# dumbpad.net
KiCad netlist of a schematic drawn in EAGLE
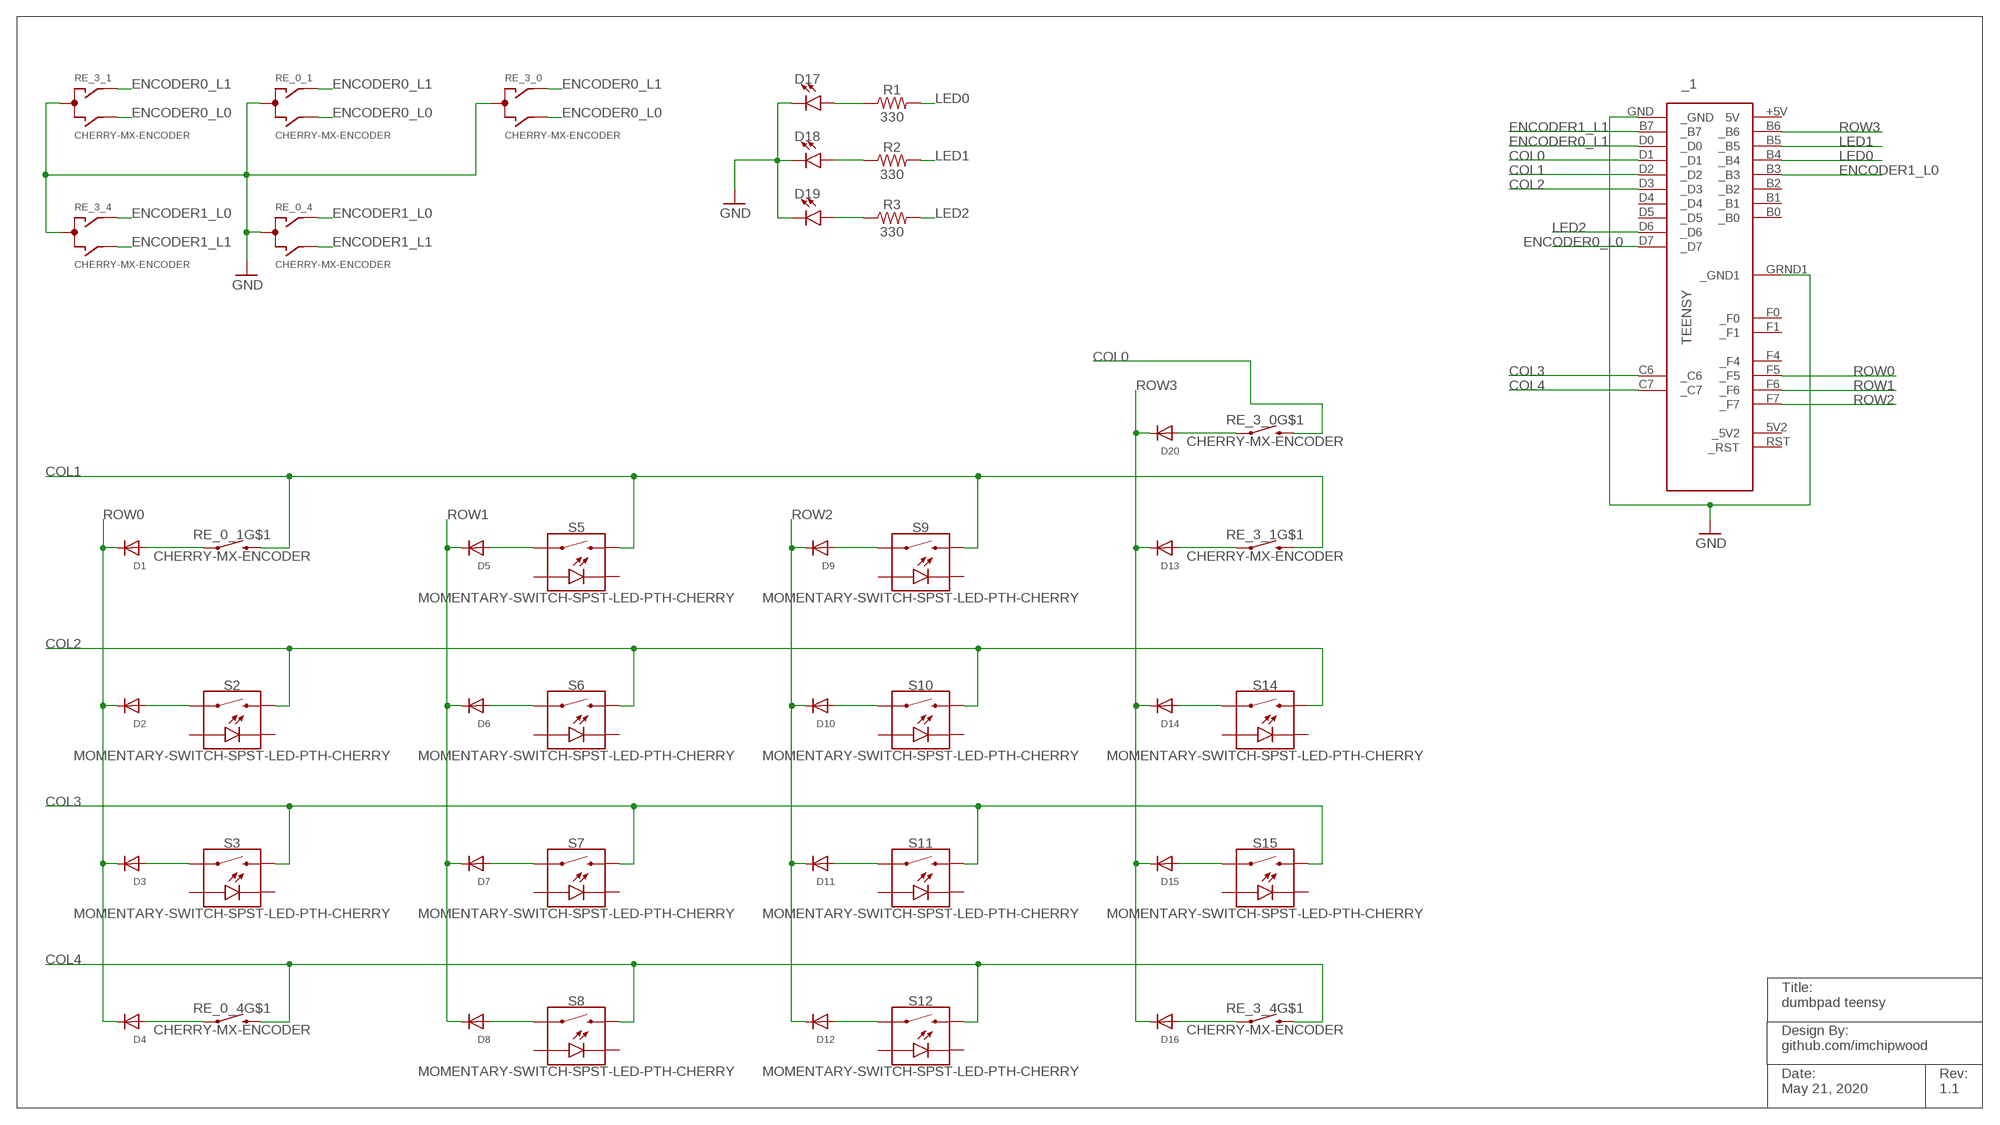
[diagram p0: schematic, sheet 1]

(export (version "E")
  (design (tool "Eeschema 10.0.6"))
  (components
    (comp (ref "D1")
      (value "DIODEDO-1N4148")
      (footprint "eagle-import:DO-1N4148")
      (libsource (lib "eagle-import") (part "DIODEDO-1N4148"))
    )
    (comp (ref "D2")
      (value "DIODEDO-1N4148")
      (footprint "eagle-import:DO-1N4148")
      (libsource (lib "eagle-import") (part "DIODEDO-1N4148"))
    )
    (comp (ref "D3")
      (value "DIODEDO-1N4148")
      (footprint "eagle-import:DO-1N4148")
      (libsource (lib "eagle-import") (part "DIODEDO-1N4148"))
    )
    (comp (ref "D4")
      (value "DIODEDO-1N4148")
      (footprint "eagle-import:DO-1N4148")
      (libsource (lib "eagle-import") (part "DIODEDO-1N4148"))
    )
    (comp (ref "D5")
      (value "DIODEDO-1N4148")
      (footprint "eagle-import:DO-1N4148")
      (libsource (lib "eagle-import") (part "DIODEDO-1N4148"))
    )
    (comp (ref "D6")
      (value "DIODEDO-1N4148")
      (footprint "eagle-import:DO-1N4148")
      (libsource (lib "eagle-import") (part "DIODEDO-1N4148"))
    )
    (comp (ref "D7")
      (value "DIODEDO-1N4148")
      (footprint "eagle-import:DO-1N4148")
      (libsource (lib "eagle-import") (part "DIODEDO-1N4148"))
    )
    (comp (ref "D8")
      (value "DIODEDO-1N4148")
      (footprint "eagle-import:DO-1N4148")
      (libsource (lib "eagle-import") (part "DIODEDO-1N4148"))
    )
    (comp (ref "D9")
      (value "DIODEDO-1N4148")
      (footprint "eagle-import:DO-1N4148")
      (libsource (lib "eagle-import") (part "DIODEDO-1N4148"))
    )
    (comp (ref "D10")
      (value "DIODEDO-1N4148")
      (footprint "eagle-import:DO-1N4148")
      (libsource (lib "eagle-import") (part "DIODEDO-1N4148"))
    )
    (comp (ref "D11")
      (value "DIODEDO-1N4148")
      (footprint "eagle-import:DO-1N4148")
      (libsource (lib "eagle-import") (part "DIODEDO-1N4148"))
    )
    (comp (ref "D12")
      (value "DIODEDO-1N4148")
      (footprint "eagle-import:DO-1N4148")
      (libsource (lib "eagle-import") (part "DIODEDO-1N4148"))
    )
    (comp (ref "D13")
      (value "DIODEDO-1N4148")
      (footprint "eagle-import:DO-1N4148")
      (libsource (lib "eagle-import") (part "DIODEDO-1N4148"))
    )
    (comp (ref "D14")
      (value "DIODEDO-1N4148")
      (footprint "eagle-import:DO-1N4148")
      (libsource (lib "eagle-import") (part "DIODEDO-1N4148"))
    )
    (comp (ref "D15")
      (value "DIODEDO-1N4148")
      (footprint "eagle-import:DO-1N4148")
      (libsource (lib "eagle-import") (part "DIODEDO-1N4148"))
    )
    (comp (ref "D16")
      (value "DIODEDO-1N4148")
      (footprint "eagle-import:DO-1N4148")
      (libsource (lib "eagle-import") (part "DIODEDO-1N4148"))
    )
    (comp (ref "D17")
      (value "LED3MM")
      (footprint "eagle-import:LED_3MM")
      (libsource (lib "eagle-import") (part "LED3MM"))
    )
    (comp (ref "D18")
      (value "LED3MM")
      (footprint "eagle-import:LED_3MM")
      (libsource (lib "eagle-import") (part "LED3MM"))
    )
    (comp (ref "D19")
      (value "LED3MM")
      (footprint "eagle-import:LED_3MM")
      (libsource (lib "eagle-import") (part "LED3MM"))
    )
    (comp (ref "D20")
      (value "DIODEDO-1N4148")
      (footprint "eagle-import:DO-1N4148")
      (libsource (lib "eagle-import") (part "DIODEDO-1N4148"))
    )
    (comp (ref "R1")
      (value "330")
      (footprint "eagle-import:AXIAL-0.3")
      (libsource (lib "eagle-import") (part "330OHM-HORIZ-1/10W-5%"))
    )
    (comp (ref "R2")
      (value "330")
      (footprint "eagle-import:AXIAL-0.3")
      (libsource (lib "eagle-import") (part "330OHM-HORIZ-1/10W-5%"))
    )
    (comp (ref "R3")
      (value "330")
      (footprint "eagle-import:AXIAL-0.3")
      (libsource (lib "eagle-import") (part "330OHM-HORIZ-1/10W-5%"))
    )
    (comp (ref "RE_0_1")
      (value "CHERRY-MX-ENCODER")
      (footprint "eagle-import:CHERRY-MX-ENCODER")
      (libsource (lib "eagle-import") (part "CHERRY-MX-ENCODER"))
    )
    (comp (ref "RE_0_4")
      (value "CHERRY-MX-ENCODER")
      (footprint "eagle-import:CHERRY-MX-ENCODER")
      (libsource (lib "eagle-import") (part "CHERRY-MX-ENCODER"))
    )
    (comp (ref "RE_3_0")
      (value "CHERRY-MX-ENCODER")
      (footprint "eagle-import:CHERRY-MX-ENCODER")
      (libsource (lib "eagle-import") (part "CHERRY-MX-ENCODER"))
    )
    (comp (ref "RE_3_1")
      (value "CHERRY-MX-ENCODER")
      (footprint "eagle-import:CHERRY-MX-ENCODER")
      (libsource (lib "eagle-import") (part "CHERRY-MX-ENCODER"))
    )
    (comp (ref "RE_3_4")
      (value "CHERRY-MX-ENCODER")
      (footprint "eagle-import:CHERRY-MX-ENCODER")
      (libsource (lib "eagle-import") (part "CHERRY-MX-ENCODER"))
    )
    (comp (ref "S2")
      (value "MOMENTARY-SWITCH-SPST-LED-PTH-CHERRY")
      (footprint "eagle-import:CHERRY-MX-LED")
      (libsource (lib "eagle-import") (part "MOMENTARY-SWITCH-SPST-LED-PTH-CHERRY"))
    )
    (comp (ref "S3")
      (value "MOMENTARY-SWITCH-SPST-LED-PTH-CHERRY")
      (footprint "eagle-import:CHERRY-MX-LED")
      (libsource (lib "eagle-import") (part "MOMENTARY-SWITCH-SPST-LED-PTH-CHERRY"))
    )
    (comp (ref "S5")
      (value "MOMENTARY-SWITCH-SPST-LED-PTH-CHERRY")
      (footprint "eagle-import:CHERRY-MX-LED")
      (libsource (lib "eagle-import") (part "MOMENTARY-SWITCH-SPST-LED-PTH-CHERRY"))
    )
    (comp (ref "S6")
      (value "MOMENTARY-SWITCH-SPST-LED-PTH-CHERRY")
      (footprint "eagle-import:CHERRY-MX-LED")
      (libsource (lib "eagle-import") (part "MOMENTARY-SWITCH-SPST-LED-PTH-CHERRY"))
    )
    (comp (ref "S7")
      (value "MOMENTARY-SWITCH-SPST-LED-PTH-CHERRY")
      (footprint "eagle-import:CHERRY-MX-LED")
      (libsource (lib "eagle-import") (part "MOMENTARY-SWITCH-SPST-LED-PTH-CHERRY"))
    )
    (comp (ref "S8")
      (value "MOMENTARY-SWITCH-SPST-LED-PTH-CHERRY")
      (footprint "eagle-import:CHERRY-MX-LED")
      (libsource (lib "eagle-import") (part "MOMENTARY-SWITCH-SPST-LED-PTH-CHERRY"))
    )
    (comp (ref "S9")
      (value "MOMENTARY-SWITCH-SPST-LED-PTH-CHERRY")
      (footprint "eagle-import:CHERRY-MX-LED")
      (libsource (lib "eagle-import") (part "MOMENTARY-SWITCH-SPST-LED-PTH-CHERRY"))
    )
    (comp (ref "S10")
      (value "MOMENTARY-SWITCH-SPST-LED-PTH-CHERRY")
      (footprint "eagle-import:CHERRY-MX-LED")
      (libsource (lib "eagle-import") (part "MOMENTARY-SWITCH-SPST-LED-PTH-CHERRY"))
    )
    (comp (ref "S11")
      (value "MOMENTARY-SWITCH-SPST-LED-PTH-CHERRY")
      (footprint "eagle-import:CHERRY-MX-LED")
      (libsource (lib "eagle-import") (part "MOMENTARY-SWITCH-SPST-LED-PTH-CHERRY"))
    )
    (comp (ref "S12")
      (value "MOMENTARY-SWITCH-SPST-LED-PTH-CHERRY")
      (footprint "eagle-import:CHERRY-MX-LED")
      (libsource (lib "eagle-import") (part "MOMENTARY-SWITCH-SPST-LED-PTH-CHERRY"))
    )
    (comp (ref "S14")
      (value "MOMENTARY-SWITCH-SPST-LED-PTH-CHERRY")
      (footprint "eagle-import:CHERRY-MX-LED")
      (libsource (lib "eagle-import") (part "MOMENTARY-SWITCH-SPST-LED-PTH-CHERRY"))
    )
    (comp (ref "S15")
      (value "MOMENTARY-SWITCH-SPST-LED-PTH-CHERRY")
      (footprint "eagle-import:CHERRY-MX-LED")
      (libsource (lib "eagle-import") (part "MOMENTARY-SWITCH-SPST-LED-PTH-CHERRY"))
    )
    (comp (ref "_1")
      (value "TEENSY")
      (footprint "eagle-import:TEENSY")
      (libsource (lib "eagle-import") (part "TEENSY"))
    )
  )
  (nets
    (net (code "1") (name "/COL0") (class "Default")
      (node (ref "RE_3_0") (pin "E") (pinfunction "2_E") (pintype "passive"))
      (node (ref "RE_3_0") (pin "S2") (pinfunction "2_S2") (pintype "passive"))
      (node (ref "_1") (pin "D1") (pinfunction "_D1_D1") (pintype "bidirectional"))
    )
    (net (code "2") (name "/COL1") (class "Default")
      (node (ref "RE_0_1") (pin "E") (pinfunction "2_E") (pintype "passive"))
      (node (ref "RE_0_1") (pin "S2") (pinfunction "2_S2") (pintype "passive"))
      (node (ref "RE_3_1") (pin "E") (pinfunction "2_E") (pintype "passive"))
      (node (ref "RE_3_1") (pin "S2") (pinfunction "2_S2") (pintype "passive"))
      (node (ref "S5") (pin "S2") (pinfunction "2_S2") (pintype "passive"))
      (node (ref "S9") (pin "S2") (pinfunction "2_S2") (pintype "passive"))
      (node (ref "_1") (pin "D2") (pinfunction "_D2_D2") (pintype "bidirectional"))
    )
    (net (code "3") (name "/COL2") (class "Default")
      (node (ref "S10") (pin "S2") (pinfunction "2_S2") (pintype "passive"))
      (node (ref "S14") (pin "S2") (pinfunction "2_S2") (pintype "passive"))
      (node (ref "S2") (pin "S2") (pinfunction "2_S2") (pintype "passive"))
      (node (ref "S6") (pin "S2") (pinfunction "2_S2") (pintype "passive"))
      (node (ref "_1") (pin "D3") (pinfunction "_D3_D3") (pintype "bidirectional"))
    )
    (net (code "4") (name "/COL3") (class "Default")
      (node (ref "S11") (pin "S2") (pinfunction "2_S2") (pintype "passive"))
      (node (ref "S15") (pin "S2") (pinfunction "2_S2") (pintype "passive"))
      (node (ref "S3") (pin "S2") (pinfunction "2_S2") (pintype "passive"))
      (node (ref "S7") (pin "S2") (pinfunction "2_S2") (pintype "passive"))
      (node (ref "_1") (pin "C6") (pinfunction "_C6_C6") (pintype "bidirectional"))
    )
    (net (code "5") (name "/COL4") (class "Default")
      (node (ref "RE_0_4") (pin "E") (pinfunction "2_E") (pintype "passive"))
      (node (ref "RE_0_4") (pin "S2") (pinfunction "2_S2") (pintype "passive"))
      (node (ref "RE_3_4") (pin "E") (pinfunction "2_E") (pintype "passive"))
      (node (ref "RE_3_4") (pin "S2") (pinfunction "2_S2") (pintype "passive"))
      (node (ref "S12") (pin "S2") (pinfunction "2_S2") (pintype "passive"))
      (node (ref "S8") (pin "S2") (pinfunction "2_S2") (pintype "passive"))
      (node (ref "_1") (pin "C7") (pinfunction "_C7_C7") (pintype "bidirectional"))
    )
    (net (code "6") (name "/ENCODER0_L0") (class "Default")
      (node (ref "RE_0_1") (pin "B") (pinfunction "B_B") (pintype "passive"))
      (node (ref "RE_3_0") (pin "B") (pinfunction "B_B") (pintype "passive"))
      (node (ref "RE_3_1") (pin "B") (pinfunction "B_B") (pintype "passive"))
      (node (ref "_1") (pin "D7") (pinfunction "_D7_D7") (pintype "bidirectional"))
    )
    (net (code "7") (name "/ENCODER0_L1") (class "Default")
      (node (ref "RE_0_1") (pin "A") (pinfunction "A_A") (pintype "passive"))
      (node (ref "RE_3_0") (pin "A") (pinfunction "A_A") (pintype "passive"))
      (node (ref "RE_3_1") (pin "A") (pinfunction "A_A") (pintype "passive"))
      (node (ref "_1") (pin "D0") (pinfunction "_D0_D0") (pintype "bidirectional"))
    )
    (net (code "8") (name "/ENCODER1_L0") (class "Default")
      (node (ref "RE_0_4") (pin "A") (pinfunction "A_A") (pintype "passive"))
      (node (ref "RE_3_4") (pin "A") (pinfunction "A_A") (pintype "passive"))
      (node (ref "_1") (pin "B3") (pinfunction "_B3_B3") (pintype "bidirectional"))
    )
    (net (code "9") (name "/ENCODER1_L1") (class "Default")
      (node (ref "RE_0_4") (pin "B") (pinfunction "B_B") (pintype "passive"))
      (node (ref "RE_3_4") (pin "B") (pinfunction "B_B") (pintype "passive"))
      (node (ref "_1") (pin "B7") (pinfunction "_B7_B7") (pintype "bidirectional"))
    )
    (net (code "10") (name "/LED0") (class "Default")
      (node (ref "R1") (pin "P$2") (pinfunction "2_P$2") (pintype "passive"))
      (node (ref "_1") (pin "B4") (pinfunction "_B4_B4") (pintype "bidirectional"))
    )
    (net (code "11") (name "/LED1") (class "Default")
      (node (ref "R2") (pin "P$2") (pinfunction "2_P$2") (pintype "passive"))
      (node (ref "_1") (pin "B5") (pinfunction "_B5_B5") (pintype "bidirectional"))
    )
    (net (code "12") (name "/LED2") (class "Default")
      (node (ref "R3") (pin "P$2") (pinfunction "2_P$2") (pintype "passive"))
      (node (ref "_1") (pin "D6") (pinfunction "_D6_D6") (pintype "bidirectional"))
    )
    (net (code "13") (name "/ROW0") (class "Default")
      (node (ref "D1") (pin "C") (pinfunction "C_C") (pintype "passive"))
      (node (ref "D2") (pin "C") (pinfunction "C_C") (pintype "passive"))
      (node (ref "D3") (pin "C") (pinfunction "C_C") (pintype "passive"))
      (node (ref "D4") (pin "C") (pinfunction "C_C") (pintype "passive"))
      (node (ref "_1") (pin "F5") (pinfunction "_F5_F5") (pintype "bidirectional"))
    )
    (net (code "14") (name "/ROW1") (class "Default")
      (node (ref "D5") (pin "C") (pinfunction "C_C") (pintype "passive"))
      (node (ref "D6") (pin "C") (pinfunction "C_C") (pintype "passive"))
      (node (ref "D7") (pin "C") (pinfunction "C_C") (pintype "passive"))
      (node (ref "D8") (pin "C") (pinfunction "C_C") (pintype "passive"))
      (node (ref "_1") (pin "F6") (pinfunction "_F6_F6") (pintype "bidirectional"))
    )
    (net (code "15") (name "/ROW2") (class "Default")
      (node (ref "D10") (pin "C") (pinfunction "C_C") (pintype "passive"))
      (node (ref "D11") (pin "C") (pinfunction "C_C") (pintype "passive"))
      (node (ref "D12") (pin "C") (pinfunction "C_C") (pintype "passive"))
      (node (ref "D9") (pin "C") (pinfunction "C_C") (pintype "passive"))
      (node (ref "_1") (pin "F7") (pinfunction "_F7_F7") (pintype "bidirectional"))
    )
    (net (code "16") (name "/ROW3") (class "Default")
      (node (ref "D13") (pin "C") (pinfunction "C_C") (pintype "passive"))
      (node (ref "D14") (pin "C") (pinfunction "C_C") (pintype "passive"))
      (node (ref "D15") (pin "C") (pinfunction "C_C") (pintype "passive"))
      (node (ref "D16") (pin "C") (pinfunction "C_C") (pintype "passive"))
      (node (ref "D20") (pin "C") (pinfunction "C_C") (pintype "passive"))
      (node (ref "_1") (pin "B6") (pinfunction "_B6_B6") (pintype "bidirectional"))
    )
    (net (code "17") (name "GND") (class "Default")
      (node (ref "D17") (pin "K") (pinfunction "C_K") (pintype "passive"))
      (node (ref "D18") (pin "K") (pinfunction "C_K") (pintype "passive"))
      (node (ref "D19") (pin "K") (pinfunction "C_K") (pintype "passive"))
      (node (ref "RE_0_1") (pin "C") (pinfunction "C_C") (pintype "passive"))
      (node (ref "RE_0_4") (pin "C") (pinfunction "C_C") (pintype "passive"))
      (node (ref "RE_3_0") (pin "C") (pinfunction "C_C") (pintype "passive"))
      (node (ref "RE_3_1") (pin "C") (pinfunction "C_C") (pintype "passive"))
      (node (ref "RE_3_4") (pin "C") (pinfunction "C_C") (pintype "passive"))
      (node (ref "_1") (pin "GND") (pinfunction "_GND_GND") (pintype "bidirectional"))
      (node (ref "_1") (pin "GRND1") (pinfunction "_GND1_GRND1") (pintype "bidirectional"))
    )
    (net (code "18") (name "Net-(D1-PadA)") (class "Default")
      (node (ref "D1") (pin "A") (pinfunction "A_A") (pintype "passive"))
      (node (ref "RE_0_1") (pin "D") (pinfunction "1_D") (pintype "passive"))
      (node (ref "RE_0_1") (pin "S1") (pinfunction "1_S1") (pintype "passive"))
    )
    (net (code "19") (name "Net-(D4-PadA)") (class "Default")
      (node (ref "D4") (pin "A") (pinfunction "A_A") (pintype "passive"))
      (node (ref "RE_0_4") (pin "D") (pinfunction "1_D") (pintype "passive"))
      (node (ref "RE_0_4") (pin "S1") (pinfunction "1_S1") (pintype "passive"))
    )
    (net (code "20") (name "Net-(D13-PadA)") (class "Default")
      (node (ref "D13") (pin "A") (pinfunction "A_A") (pintype "passive"))
      (node (ref "RE_3_1") (pin "D") (pinfunction "1_D") (pintype "passive"))
      (node (ref "RE_3_1") (pin "S1") (pinfunction "1_S1") (pintype "passive"))
    )
    (net (code "21") (name "Net-(D16-PadA)") (class "Default")
      (node (ref "D16") (pin "A") (pinfunction "A_A") (pintype "passive"))
      (node (ref "RE_3_4") (pin "D") (pinfunction "1_D") (pintype "passive"))
      (node (ref "RE_3_4") (pin "S1") (pinfunction "1_S1") (pintype "passive"))
    )
    (net (code "22") (name "Net-(D20-PadA)") (class "Default")
      (node (ref "D20") (pin "A") (pinfunction "A_A") (pintype "passive"))
      (node (ref "RE_3_0") (pin "D") (pinfunction "1_D") (pintype "passive"))
      (node (ref "RE_3_0") (pin "S1") (pinfunction "1_S1") (pintype "passive"))
    )
    (net (code "23") (name "Net-(R1-1)") (class "Default")
      (node (ref "D17") (pin "A") (pinfunction "A_A") (pintype "passive"))
      (node (ref "R1") (pin "P$1") (pinfunction "1_P$1") (pintype "passive"))
    )
    (net (code "24") (name "Net-(R2-1)") (class "Default")
      (node (ref "D18") (pin "A") (pinfunction "A_A") (pintype "passive"))
      (node (ref "R2") (pin "P$1") (pinfunction "1_P$1") (pintype "passive"))
    )
    (net (code "25") (name "Net-(R3-1)") (class "Default")
      (node (ref "D19") (pin "A") (pinfunction "A_A") (pintype "passive"))
      (node (ref "R3") (pin "P$1") (pinfunction "1_P$1") (pintype "passive"))
    )
    (net (code "26") (name "Net-(S2-1)") (class "Default")
      (node (ref "D2") (pin "A") (pinfunction "A_A") (pintype "passive"))
      (node (ref "S2") (pin "S1") (pinfunction "1_S1") (pintype "passive"))
    )
    (net (code "27") (name "Net-(S3-1)") (class "Default")
      (node (ref "D3") (pin "A") (pinfunction "A_A") (pintype "passive"))
      (node (ref "S3") (pin "S1") (pinfunction "1_S1") (pintype "passive"))
    )
    (net (code "28") (name "Net-(S5-1)") (class "Default")
      (node (ref "D5") (pin "A") (pinfunction "A_A") (pintype "passive"))
      (node (ref "S5") (pin "S1") (pinfunction "1_S1") (pintype "passive"))
    )
    (net (code "29") (name "Net-(S6-1)") (class "Default")
      (node (ref "D6") (pin "A") (pinfunction "A_A") (pintype "passive"))
      (node (ref "S6") (pin "S1") (pinfunction "1_S1") (pintype "passive"))
    )
    (net (code "30") (name "Net-(S7-1)") (class "Default")
      (node (ref "D7") (pin "A") (pinfunction "A_A") (pintype "passive"))
      (node (ref "S7") (pin "S1") (pinfunction "1_S1") (pintype "passive"))
    )
    (net (code "31") (name "Net-(S8-1)") (class "Default")
      (node (ref "D8") (pin "A") (pinfunction "A_A") (pintype "passive"))
      (node (ref "S8") (pin "S1") (pinfunction "1_S1") (pintype "passive"))
    )
    (net (code "32") (name "Net-(S9-1)") (class "Default")
      (node (ref "D9") (pin "A") (pinfunction "A_A") (pintype "passive"))
      (node (ref "S9") (pin "S1") (pinfunction "1_S1") (pintype "passive"))
    )
    (net (code "33") (name "Net-(S10-1)") (class "Default")
      (node (ref "D10") (pin "A") (pinfunction "A_A") (pintype "passive"))
      (node (ref "S10") (pin "S1") (pinfunction "1_S1") (pintype "passive"))
    )
    (net (code "34") (name "Net-(S11-1)") (class "Default")
      (node (ref "D11") (pin "A") (pinfunction "A_A") (pintype "passive"))
      (node (ref "S11") (pin "S1") (pinfunction "1_S1") (pintype "passive"))
    )
    (net (code "35") (name "Net-(S12-1)") (class "Default")
      (node (ref "D12") (pin "A") (pinfunction "A_A") (pintype "passive"))
      (node (ref "S12") (pin "S1") (pinfunction "1_S1") (pintype "passive"))
    )
    (net (code "36") (name "Net-(S14-1)") (class "Default")
      (node (ref "D14") (pin "A") (pinfunction "A_A") (pintype "passive"))
      (node (ref "S14") (pin "S1") (pinfunction "1_S1") (pintype "passive"))
    )
    (net (code "37") (name "Net-(S15-1)") (class "Default")
      (node (ref "D15") (pin "A") (pinfunction "A_A") (pintype "passive"))
      (node (ref "S15") (pin "S1") (pinfunction "1_S1") (pintype "passive"))
    )
    (net (code "38") (name "unconnected-(S2-C-PadK)") (class "Default")
      (node (ref "S2") (pin "K") (pinfunction "C_K") (pintype "passive"))
    )
    (net (code "39") (name "unconnected-(S2-PadA)") (class "Default")
      (node (ref "S2") (pin "A") (pinfunction "A_A") (pintype "passive"))
    )
    (net (code "40") (name "unconnected-(S3-C-PadK)") (class "Default")
      (node (ref "S3") (pin "K") (pinfunction "C_K") (pintype "passive"))
    )
    (net (code "41") (name "unconnected-(S3-PadA)") (class "Default")
      (node (ref "S3") (pin "A") (pinfunction "A_A") (pintype "passive"))
    )
    (net (code "42") (name "unconnected-(S5-C-PadK)") (class "Default")
      (node (ref "S5") (pin "K") (pinfunction "C_K") (pintype "passive"))
    )
    (net (code "43") (name "unconnected-(S5-PadA)") (class "Default")
      (node (ref "S5") (pin "A") (pinfunction "A_A") (pintype "passive"))
    )
    (net (code "44") (name "unconnected-(S6-C-PadK)") (class "Default")
      (node (ref "S6") (pin "K") (pinfunction "C_K") (pintype "passive"))
    )
    (net (code "45") (name "unconnected-(S6-PadA)") (class "Default")
      (node (ref "S6") (pin "A") (pinfunction "A_A") (pintype "passive"))
    )
    (net (code "46") (name "unconnected-(S7-C-PadK)") (class "Default")
      (node (ref "S7") (pin "K") (pinfunction "C_K") (pintype "passive"))
    )
    (net (code "47") (name "unconnected-(S7-PadA)") (class "Default")
      (node (ref "S7") (pin "A") (pinfunction "A_A") (pintype "passive"))
    )
    (net (code "48") (name "unconnected-(S8-C-PadK)") (class "Default")
      (node (ref "S8") (pin "K") (pinfunction "C_K") (pintype "passive"))
    )
    (net (code "49") (name "unconnected-(S8-PadA)") (class "Default")
      (node (ref "S8") (pin "A") (pinfunction "A_A") (pintype "passive"))
    )
    (net (code "50") (name "unconnected-(S9-C-PadK)") (class "Default")
      (node (ref "S9") (pin "K") (pinfunction "C_K") (pintype "passive"))
    )
    (net (code "51") (name "unconnected-(S9-PadA)") (class "Default")
      (node (ref "S9") (pin "A") (pinfunction "A_A") (pintype "passive"))
    )
    (net (code "52") (name "unconnected-(S10-C-PadK)") (class "Default")
      (node (ref "S10") (pin "K") (pinfunction "C_K") (pintype "passive"))
    )
    (net (code "53") (name "unconnected-(S10-PadA)") (class "Default")
      (node (ref "S10") (pin "A") (pinfunction "A_A") (pintype "passive"))
    )
    (net (code "54") (name "unconnected-(S11-C-PadK)") (class "Default")
      (node (ref "S11") (pin "K") (pinfunction "C_K") (pintype "passive"))
    )
    (net (code "55") (name "unconnected-(S11-PadA)") (class "Default")
      (node (ref "S11") (pin "A") (pinfunction "A_A") (pintype "passive"))
    )
    (net (code "56") (name "unconnected-(S12-C-PadK)") (class "Default")
      (node (ref "S12") (pin "K") (pinfunction "C_K") (pintype "passive"))
    )
    (net (code "57") (name "unconnected-(S12-PadA)") (class "Default")
      (node (ref "S12") (pin "A") (pinfunction "A_A") (pintype "passive"))
    )
    (net (code "58") (name "unconnected-(S14-C-PadK)") (class "Default")
      (node (ref "S14") (pin "K") (pinfunction "C_K") (pintype "passive"))
    )
    (net (code "59") (name "unconnected-(S14-PadA)") (class "Default")
      (node (ref "S14") (pin "A") (pinfunction "A_A") (pintype "passive"))
    )
    (net (code "60") (name "unconnected-(S15-C-PadK)") (class "Default")
      (node (ref "S15") (pin "K") (pinfunction "C_K") (pintype "passive"))
    )
    (net (code "61") (name "unconnected-(S15-PadA)") (class "Default")
      (node (ref "S15") (pin "A") (pinfunction "A_A") (pintype "passive"))
    )
    (net (code "62") (name "unconnected-(_1-5V-Pad+5V)") (class "Default")
      (node (ref "_1") (pin "+5V") (pinfunction "5V_+5V") (pintype "bidirectional"))
    )
    (net (code "63") (name "unconnected-(_1-_5V2-Pad5V2)") (class "Default")
      (node (ref "_1") (pin "5V2") (pinfunction "_5V2_5V2") (pintype "bidirectional"))
    )
    (net (code "64") (name "unconnected-(_1-_B0-PadB0)") (class "Default")
      (node (ref "_1") (pin "B0") (pinfunction "_B0_B0") (pintype "bidirectional"))
    )
    (net (code "65") (name "unconnected-(_1-_B1-PadB1)") (class "Default")
      (node (ref "_1") (pin "B1") (pinfunction "_B1_B1") (pintype "bidirectional"))
    )
    (net (code "66") (name "unconnected-(_1-_B2-PadB2)") (class "Default")
      (node (ref "_1") (pin "B2") (pinfunction "_B2_B2") (pintype "bidirectional"))
    )
    (net (code "67") (name "unconnected-(_1-_D4-PadD4)") (class "Default")
      (node (ref "_1") (pin "D4") (pinfunction "_D4_D4") (pintype "bidirectional"))
    )
    (net (code "68") (name "unconnected-(_1-_D5-PadD5)") (class "Default")
      (node (ref "_1") (pin "D5") (pinfunction "_D5_D5") (pintype "bidirectional"))
    )
    (net (code "69") (name "unconnected-(_1-_F0-PadF0)") (class "Default")
      (node (ref "_1") (pin "F0") (pinfunction "_F0_F0") (pintype "bidirectional"))
    )
    (net (code "70") (name "unconnected-(_1-_F1-PadF1)") (class "Default")
      (node (ref "_1") (pin "F1") (pinfunction "_F1_F1") (pintype "bidirectional"))
    )
    (net (code "71") (name "unconnected-(_1-_F4-PadF4)") (class "Default")
      (node (ref "_1") (pin "F4") (pinfunction "_F4_F4") (pintype "bidirectional"))
    )
    (net (code "72") (name "unconnected-(_1-_RST-PadRST)") (class "Default")
      (node (ref "_1") (pin "RST") (pinfunction "_RST_RST") (pintype "bidirectional"))
    )
  )
)
